# EE209_Schematic.net
KiCad netlist of a schematic drawn in Altium Designer
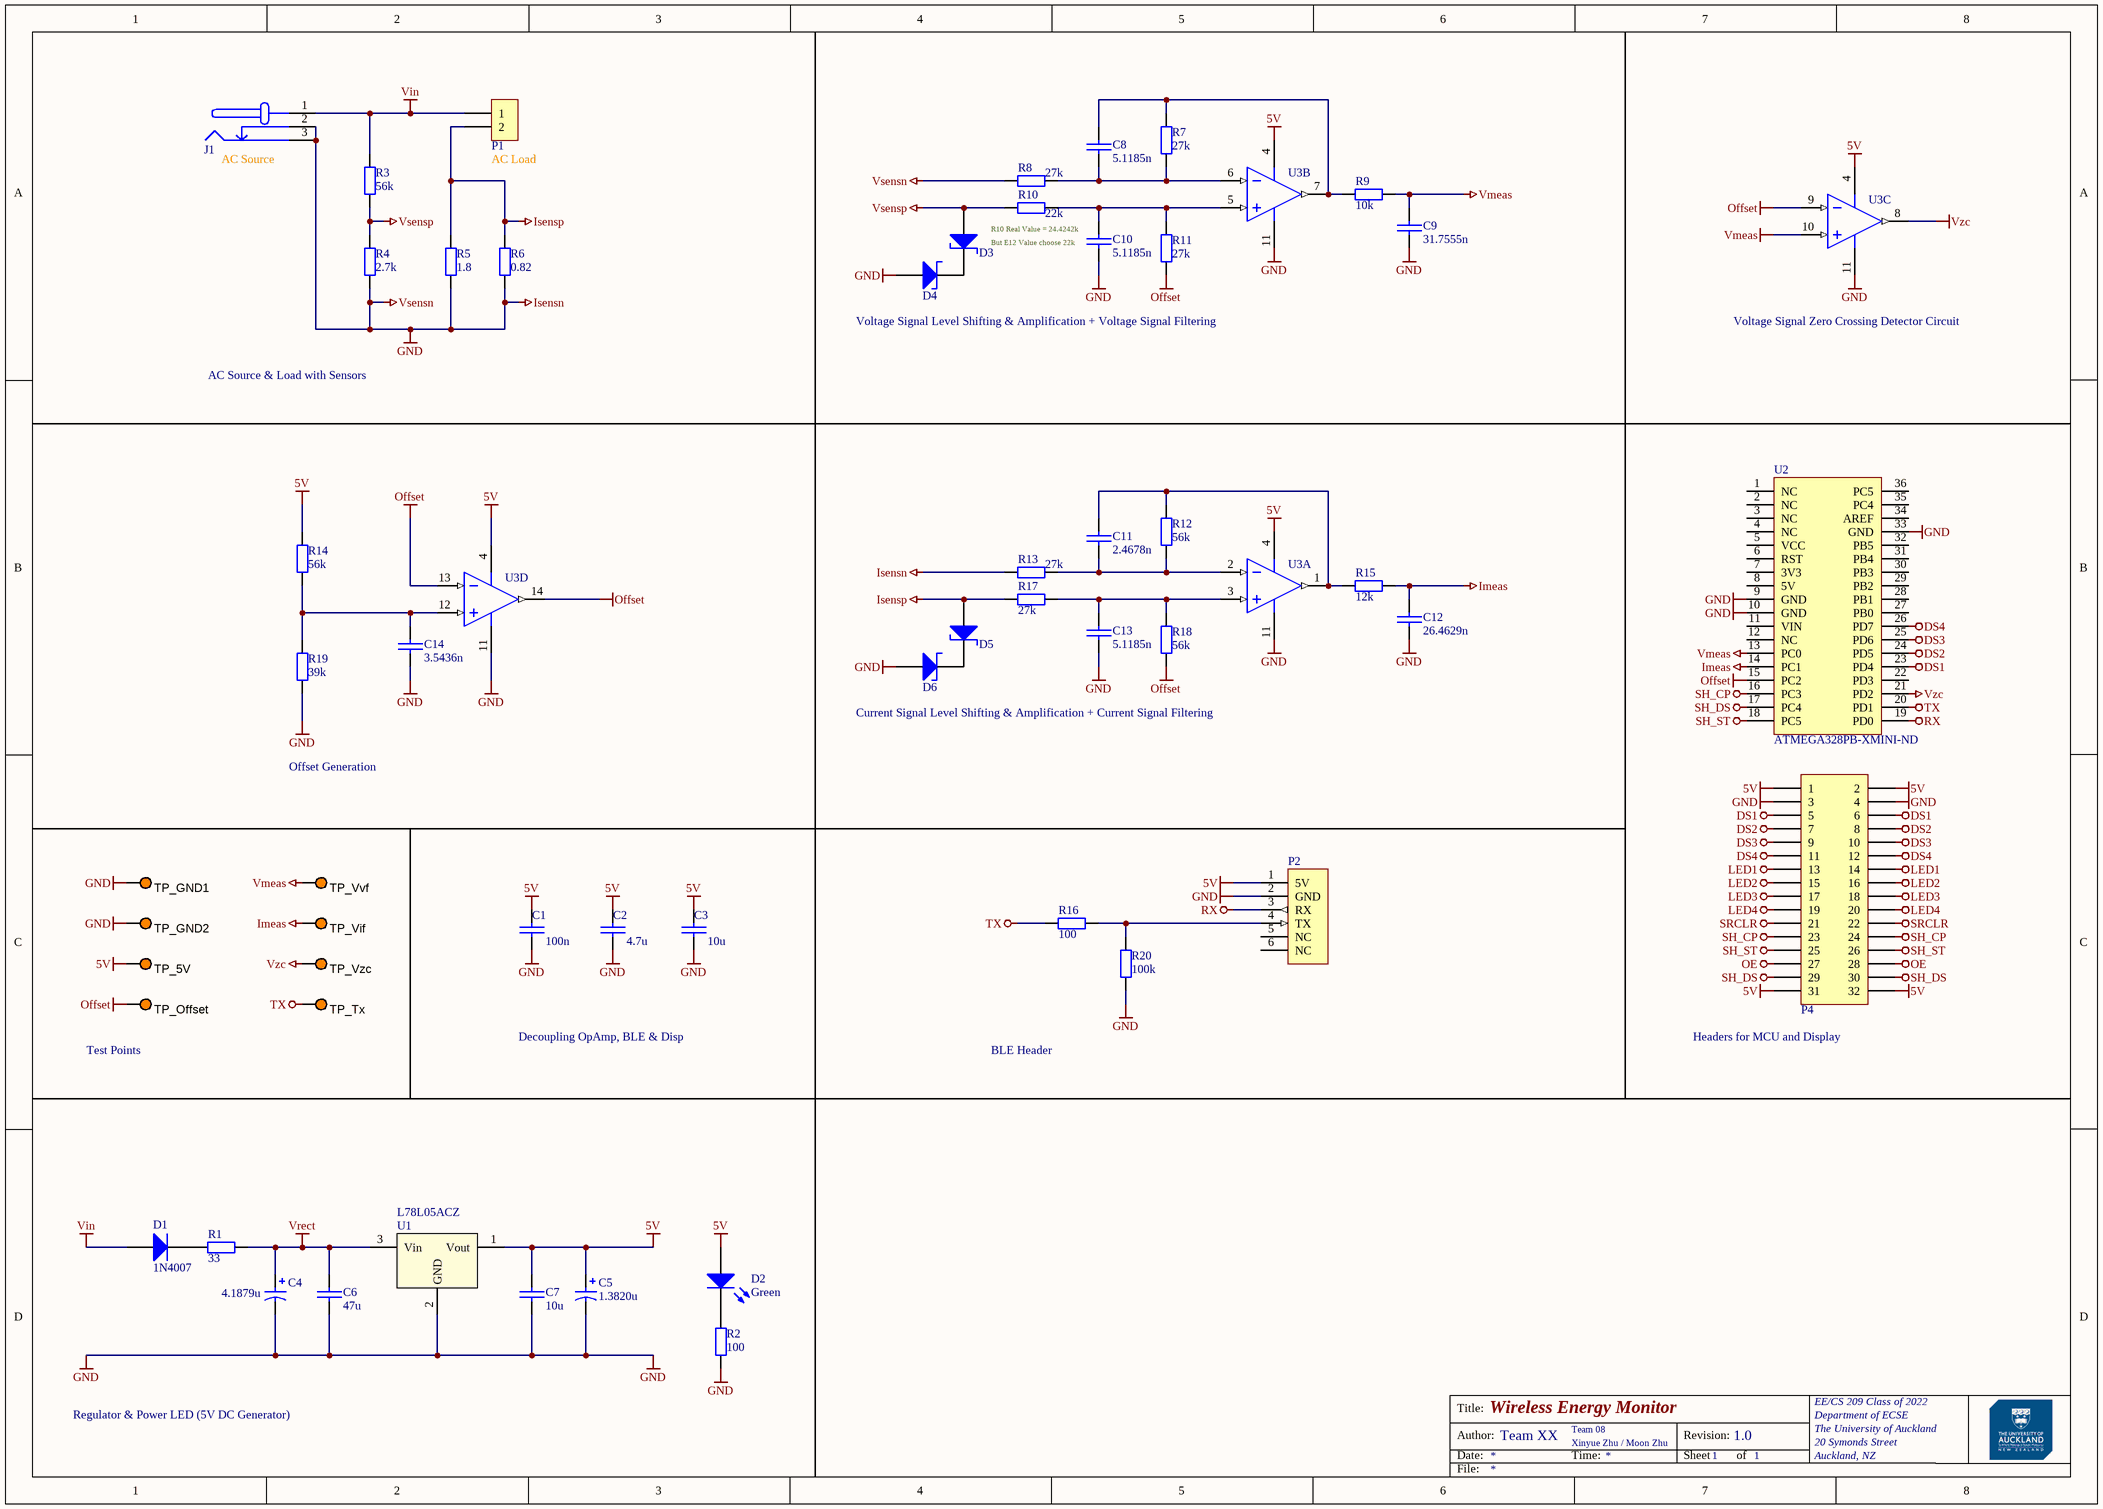
[diagram p0: EE209_Schematic.SchDoc]

(export (version "E")
  (design (tool "Eeschema 10.0.6"))
  (components
    (comp (ref "C1")
      (value "100n")
      (footprint "CCAP-5P0")
      (description "TH ceramic capacitor with 5mm pitch")
      (libsource (lib "EE209_Library") (part "CerCap_TH_5P0"))
    )
    (comp (ref "C2")
      (value "4.7u")
      (footprint "CCAP-5P0")
      (description "TH ceramic capacitor with 5mm pitch")
      (libsource (lib "EE209_Library") (part "CerCap_TH_5P0"))
    )
    (comp (ref "C3")
      (value "10u")
      (footprint "CCAP-5P0")
      (description "TH ceramic capacitor with 5mm pitch")
      (libsource (lib "EE209_Library") (part "CerCap_TH_5P0"))
    )
    (comp (ref "C4")
      (value "4.1879u")
      (footprint "CAP-RAD-2.5mm Pitch")
      (description "Electrolytic capacitor with radial package, 2mm pitch and 5.2mm diameter")
      (fields (field (name "PUBLISHER") "Altium Limited"))
      (libsource (lib "EE209_Library") (part "ElecCap_TH_2P0"))
    )
    (comp (ref "C5")
      (value "1.3820u")
      (footprint "CAP-RAD-2.5mm Pitch")
      (description "Electrolytic capacitor with radial package, 2mm pitch and 5.2mm diameter")
      (fields (field (name "PUBLISHER") "Altium Limited"))
      (libsource (lib "EE209_Library") (part "ElecCap_TH_2P0"))
    )
    (comp (ref "C6")
      (value "47u")
      (footprint "CCAP-5P0")
      (description "TH ceramic capacitor with 5mm pitch")
      (libsource (lib "EE209_Library") (part "CerCap_TH_5P0"))
    )
    (comp (ref "C7")
      (value "10u")
      (footprint "CCAP-5P0")
      (description "TH ceramic capacitor with 5mm pitch")
      (libsource (lib "EE209_Library") (part "CerCap_TH_5P0"))
    )
    (comp (ref "C8")
      (value "5.1185n")
      (footprint "CCAP-5P0")
      (description "TH ceramic capacitor with 5mm pitch")
      (libsource (lib "EE209_Library") (part "CerCap_TH_5P0"))
    )
    (comp (ref "C9")
      (value "31.7555n")
      (footprint "CCAP-5P0")
      (description "TH ceramic capacitor with 5mm pitch")
      (libsource (lib "EE209_Library") (part "CerCap_TH_5P0"))
    )
    (comp (ref "C10")
      (value "5.1185n")
      (footprint "CCAP-5P0")
      (description "TH ceramic capacitor with 5mm pitch")
      (libsource (lib "EE209_Library") (part "CerCap_TH_5P0"))
    )
    (comp (ref "C11")
      (value "2.4678n")
      (footprint "CCAP-5P0")
      (description "TH ceramic capacitor with 5mm pitch")
      (libsource (lib "EE209_Library") (part "CerCap_TH_5P0"))
    )
    (comp (ref "C12")
      (value "26.4629n")
      (footprint "CCAP-5P0")
      (description "TH ceramic capacitor with 5mm pitch")
      (libsource (lib "EE209_Library") (part "CerCap_TH_5P0"))
    )
    (comp (ref "C13")
      (value "5.1185n")
      (footprint "CCAP-5P0")
      (description "TH ceramic capacitor with 5mm pitch")
      (libsource (lib "EE209_Library") (part "CerCap_TH_5P0"))
    )
    (comp (ref "C14")
      (value "3.5436n")
      (footprint "CCAP-5P0")
      (description "TH ceramic capacitor with 5mm pitch")
      (libsource (lib "EE209_Library") (part "CerCap_TH_5P0"))
    )
    (comp (ref "D1")
      (value "1N4007")
      (footprint "1N4007-MFG")
      (description "1N4007 1000V standard axial diode")
      (libsource (lib "EE209_Library") (part "1N4007_TH_4AX0"))
    )
    (comp (ref "D2")
      (value "Green")
      (footprint "LED")
      (description "Typical throughole GaAs LED with 2.54mm pitch")
      (fields (field (name "MANUFACTURER") "Generic Components") (field (name "PUBLISHER") "Altium Limited"))
      (libsource (lib "EE209_Library") (part "LED_TH_2P54"))
    )
    (comp (ref "D3")
      (value "BZX79-CXVX")
      (footprint "AXIAL-Zener-0.4")
      (description "Axial zener diode BZX79 series")
      (fields
        (field (name "MANUFACTURER") "Nexperia USA Inc.")
        (field (name "MANUFACTURER PART NUMBER") "BZX79-C4V7,143")
      )
      (libsource (lib "EE209_Library") (part "Zener_TH_4AX0"))
    )
    (comp (ref "D4")
      (value "BZX79-CXVX")
      (footprint "AXIAL-Zener-0.4")
      (description "Axial zener diode BZX79 series")
      (fields
        (field (name "MANUFACTURER") "Nexperia USA Inc.")
        (field (name "MANUFACTURER PART NUMBER") "BZX79-C4V7,143")
      )
      (libsource (lib "EE209_Library") (part "Zener_TH_4AX0"))
    )
    (comp (ref "D5")
      (value "BZX79-CXVX")
      (footprint "AXIAL-Zener-0.4")
      (description "Axial zener diode BZX79 series")
      (fields
        (field (name "MANUFACTURER") "Nexperia USA Inc.")
        (field (name "MANUFACTURER PART NUMBER") "BZX79-C4V7,143")
      )
      (libsource (lib "EE209_Library") (part "Zener_TH_4AX0"))
    )
    (comp (ref "D6")
      (value "BZX79-CXVX")
      (footprint "AXIAL-Zener-0.4")
      (description "Axial zener diode BZX79 series")
      (fields
        (field (name "MANUFACTURER") "Nexperia USA Inc.")
        (field (name "MANUFACTURER PART NUMBER") "BZX79-C4V7,143")
      )
      (libsource (lib "EE209_Library") (part "Zener_TH_4AX0"))
    )
    (comp (ref "J1")
      (value "DC barrel jack")
      (footprint "AC-Socket")
      (description "DC barrel jack connection to AC source")
      (libsource (lib "EE209_Library") (part "AC_Input"))
    )
    (comp (ref "P1")
      (value "Dual Banana Plugs")
      (footprint "Dual Banana Plug")
      (description "Dual banana plugs connection to the AC load")
      (fields (field (name "PUBLISHER") "Altium Limited"))
      (libsource (lib "EE209_Library") (part "AC_Output"))
    )
    (comp (ref "P2")
      (value "BLE Module Header")
      (footprint "HM10_HDR1X6")
      (description "2.54mm pitch 6-pin header for BLE module")
      (fields (field (name "PUBLISHER") "Altium Limited"))
      (libsource (lib "EE209_Library") (part "BLEModule_TH"))
    )
    (comp (ref "P4")
      (value "Display")
      (footprint "Display")
      (description "16-Pin Header Connecting Display")
      (libsource (lib "EE209_Library") (part "Display"))
    )
    (comp (ref "R1")
      (value "33")
      (footprint "AXIAL-0.4")
      (description "Through hole resistor")
      (fields (field (name "PUBLISHER") "Altium Limited"))
      (libsource (lib "") (part "Res_TH_0AX4_3"))
    )
    (comp (ref "R2")
      (value "100")
      (footprint "AXIAL-0.4")
      (description "Through hole resistor")
      (fields (field (name "PUBLISHER") "Altium Limited"))
      (libsource (lib "") (part "Res_TH_0AX4_1"))
    )
    (comp (ref "R3")
      (value "56k")
      (footprint "AXIAL-0.4")
      (description "Through hole resistor")
      (fields (field (name "PUBLISHER") "Altium Limited"))
      (libsource (lib "") (part "Res_TH_0AX4_1"))
    )
    (comp (ref "R4")
      (value "2.7k")
      (footprint "AXIAL-0.4")
      (description "Through hole resistor")
      (fields (field (name "PUBLISHER") "Altium Limited"))
      (libsource (lib "") (part "Res_TH_0AX4_1"))
    )
    (comp (ref "R5")
      (value "1.8")
      (footprint "AXIAL-0.4")
      (description "Through hole resistor")
      (fields (field (name "PUBLISHER") "Altium Limited"))
      (libsource (lib "") (part "Res_TH_0AX4_1"))
    )
    (comp (ref "R6")
      (value "0.82")
      (footprint "AXIAL-0.4")
      (description "Through hole resistor")
      (fields (field (name "PUBLISHER") "Altium Limited"))
      (libsource (lib "") (part "Res_TH_0AX4_1"))
    )
    (comp (ref "R7")
      (value "27k")
      (footprint "AXIAL-0.4")
      (description "Through hole resistor")
      (fields (field (name "PUBLISHER") "Altium Limited"))
      (libsource (lib "") (part "Res_TH_0AX4_1"))
    )
    (comp (ref "R8")
      (value "27k")
      (footprint "AXIAL-0.4")
      (description "Through hole resistor")
      (fields (field (name "PUBLISHER") "Altium Limited"))
      (libsource (lib "") (part "Res_TH_0AX4_2"))
    )
    (comp (ref "R9")
      (value "10k")
      (footprint "AXIAL-0.4")
      (description "Through hole resistor")
      (fields (field (name "PUBLISHER") "Altium Limited"))
      (libsource (lib "") (part "Res_TH_0AX4_2"))
    )
    (comp (ref "R10")
      (value "22k")
      (footprint "AXIAL-0.4")
      (description "Through hole resistor")
      (fields (field (name "PUBLISHER") "Altium Limited"))
      (libsource (lib "") (part "Res_TH_0AX4_2"))
    )
    (comp (ref "R11")
      (value "27k")
      (footprint "AXIAL-0.4")
      (description "Through hole resistor")
      (fields (field (name "PUBLISHER") "Altium Limited"))
      (libsource (lib "") (part "Res_TH_0AX4_1"))
    )
    (comp (ref "R12")
      (value "56k")
      (footprint "AXIAL-0.4")
      (description "Through hole resistor")
      (fields (field (name "PUBLISHER") "Altium Limited"))
      (libsource (lib "") (part "Res_TH_0AX4_1"))
    )
    (comp (ref "R13")
      (value "27k")
      (footprint "AXIAL-0.4")
      (description "Through hole resistor")
      (fields (field (name "PUBLISHER") "Altium Limited"))
      (libsource (lib "") (part "Res_TH_0AX4_2"))
    )
    (comp (ref "R14")
      (value "56k")
      (footprint "AXIAL-0.4")
      (description "Through hole resistor")
      (fields (field (name "PUBLISHER") "Altium Limited"))
      (libsource (lib "EE209_Library") (part "Res_TH_0AX4"))
    )
    (comp (ref "R15")
      (value "12k")
      (footprint "AXIAL-0.4")
      (description "Through hole resistor")
      (fields (field (name "PUBLISHER") "Altium Limited"))
      (libsource (lib "") (part "Res_TH_0AX4_2"))
    )
    (comp (ref "R16")
      (value "100")
      (footprint "AXIAL-0.4")
      (description "Through hole resistor")
      (fields (field (name "PUBLISHER") "Altium Limited"))
      (libsource (lib "") (part "Res_TH_0AX4_3"))
    )
    (comp (ref "R17")
      (value "27k")
      (footprint "AXIAL-0.4")
      (description "Through hole resistor")
      (fields (field (name "PUBLISHER") "Altium Limited"))
      (libsource (lib "") (part "Res_TH_0AX4_2"))
    )
    (comp (ref "R18")
      (value "56k")
      (footprint "AXIAL-0.4")
      (description "Through hole resistor")
      (fields (field (name "PUBLISHER") "Altium Limited"))
      (libsource (lib "") (part "Res_TH_0AX4_1"))
    )
    (comp (ref "R19")
      (value "39k")
      (footprint "AXIAL-0.4")
      (description "Through hole resistor")
      (fields (field (name "PUBLISHER") "Altium Limited"))
      (libsource (lib "") (part "Res_TH_0AX4_1"))
    )
    (comp (ref "R20")
      (value "100k")
      (footprint "AXIAL-0.4")
      (description "Through hole resistor")
      (fields (field (name "PUBLISHER") "Altium Limited"))
      (libsource (lib "") (part "Res_TH_0AX4_1"))
    )
    (comp (ref "TP_5V")
      (value "5003")
      (footprint "TP_TH")
      (description "Test Point, Orange, 1-Pin THD, RoHS")
      (libsource (lib "EE209_Library") (part "TestPoint"))
    )
    (comp (ref "TP_GND1")
      (value "5003")
      (footprint "TP_TH")
      (description "Test Point, Orange, 1-Pin THD, RoHS")
      (libsource (lib "EE209_Library") (part "TestPoint"))
    )
    (comp (ref "TP_GND2")
      (value "5003")
      (footprint "TP_TH")
      (description "Test Point, Orange, 1-Pin THD, RoHS")
      (libsource (lib "EE209_Library") (part "TestPoint"))
    )
    (comp (ref "TP_Offset")
      (value "5003")
      (footprint "TP_TH")
      (description "Test Point, Orange, 1-Pin THD, RoHS")
      (libsource (lib "EE209_Library") (part "TestPoint"))
    )
    (comp (ref "TP_Tx")
      (value "5003")
      (footprint "TP_TH")
      (description "Test Point, Orange, 1-Pin THD, RoHS")
      (libsource (lib "EE209_Library") (part "TestPoint"))
    )
    (comp (ref "TP_Vif")
      (value "5003")
      (footprint "TP_TH")
      (description "Test Point, Orange, 1-Pin THD, RoHS")
      (libsource (lib "EE209_Library") (part "TestPoint"))
    )
    (comp (ref "TP_Vvf")
      (value "5003")
      (footprint "TP_TH")
      (description "Test Point, Orange, 1-Pin THD, RoHS")
      (libsource (lib "EE209_Library") (part "TestPoint"))
    )
    (comp (ref "TP_Vzc")
      (value "5003")
      (footprint "TP_TH")
      (description "Test Point, Orange, 1-Pin THD, RoHS")
      (libsource (lib "EE209_Library") (part "TestPoint"))
    )
    (comp (ref "U1")
      (value "L78L05ACZ")
      (footprint "TO-92")
      (description "Voltage Regulator 5V")
      (fields
        (field (name "MANUFACTURER") "ON Semiconductor")
        (field (name "MANUFACTURER PART NUMBER") "LM78L05ACZX")
      )
      (libsource (lib "EE209_Library") (part "L78L05_TH_TO92"))
    )
    (comp (ref "U2")
      (value "ATmega328PB Xplained Mini Header")
      (footprint "ATmeg328P Xplained")
      (description "Dual 18-pin headers connecting to ATmega328PB Xplained Mini")
      (fields
        (field (name "MANUFACTURER") "Microchip Technology")
        (field (name "MANUFACTURER PART NUMBER") "ATMEGA328PB-XMINI")
        (field (name "SUPPLIER PART NUMBER 1") "ATMEGA328PB-XMINI-ND")
      )
      (libsource (lib "EE209_Library") (part "ATmega328PBXplained_TH"))
    )
    (comp (ref "U3")
      (value "LM324")
      (footprint "DIP-14")
      (description "IC OPAMP GP 14DIP")
      (fields
        (field (name "MANUFACTURER") "ON Semiconductor")
        (field (name "MANUFACTURER PART NUMBER") "LM324N")
      )
      (libsource (lib "EE209_Library") (part "LM324N_TH_DIP16"))
    )
  )
  (nets
    (net (code "1") (name "5V") (class "Default")
      (node (ref "C1") (pin "1") (pinfunction "1_1") (pintype "passive"))
      (node (ref "C2") (pin "1") (pinfunction "1_1") (pintype "passive"))
      (node (ref "C3") (pin "1") (pinfunction "1_1") (pintype "passive"))
      (node (ref "C5") (pin "1") (pinfunction "1_1") (pintype "passive"))
      (node (ref "C7") (pin "1") (pinfunction "1_1") (pintype "passive"))
      (node (ref "D2") (pin "1") (pinfunction "A_1") (pintype "passive"))
      (node (ref "P2") (pin "1") (pinfunction "5V_1") (pintype "passive"))
      (node (ref "P4") (pin "1") (pinfunction "1_1") (pintype "passive"))
      (node (ref "P4") (pin "2") (pinfunction "2_2") (pintype "passive"))
      (node (ref "P4") (pin "31") (pinfunction "31_31") (pintype "passive"))
      (node (ref "P4") (pin "32") (pinfunction "32_32") (pintype "passive"))
      (node (ref "R14") (pin "1") (pinfunction "1_1") (pintype "passive"))
      (node (ref "TP_5V") (pin "1") (pinfunction "1_1") (pintype "passive"))
      (node (ref "U1") (pin "1") (pinfunction "Vout_1") (pintype "passive"))
      (node (ref "U3") (pin "4") (pinfunction "VDD_4") (pintype "power_in"))
    )
    (net (code "2") (name "DS1") (class "Default")
      (node (ref "P4") (pin "5") (pinfunction "5_5") (pintype "passive"))
      (node (ref "P4") (pin "6") (pinfunction "6_6") (pintype "passive"))
      (node (ref "U2") (pin "23") (pinfunction "PD4_23") (pintype "passive"))
    )
    (net (code "3") (name "DS2") (class "Default")
      (node (ref "P4") (pin "7") (pinfunction "7_7") (pintype "passive"))
      (node (ref "P4") (pin "8") (pinfunction "8_8") (pintype "passive"))
      (node (ref "U2") (pin "24") (pinfunction "PD5_24") (pintype "passive"))
    )
    (net (code "4") (name "DS3") (class "Default")
      (node (ref "P4") (pin "10") (pinfunction "10_10") (pintype "passive"))
      (node (ref "P4") (pin "9") (pinfunction "9_9") (pintype "passive"))
      (node (ref "U2") (pin "25") (pinfunction "PD6_25") (pintype "passive"))
    )
    (net (code "5") (name "DS4") (class "Default")
      (node (ref "P4") (pin "11") (pinfunction "11_11") (pintype "passive"))
      (node (ref "P4") (pin "12") (pinfunction "12_12") (pintype "passive"))
      (node (ref "U2") (pin "26") (pinfunction "PD7_26") (pintype "passive"))
    )
    (net (code "6") (name "GND") (class "Default")
      (node (ref "C1") (pin "2") (pinfunction "2_2") (pintype "passive"))
      (node (ref "C10") (pin "2") (pinfunction "2_2") (pintype "passive"))
      (node (ref "C12") (pin "2") (pinfunction "2_2") (pintype "passive"))
      (node (ref "C13") (pin "2") (pinfunction "2_2") (pintype "passive"))
      (node (ref "C14") (pin "2") (pinfunction "2_2") (pintype "passive"))
      (node (ref "C2") (pin "2") (pinfunction "2_2") (pintype "passive"))
      (node (ref "C3") (pin "2") (pinfunction "2_2") (pintype "passive"))
      (node (ref "C4") (pin "2") (pinfunction "2_2") (pintype "passive"))
      (node (ref "C5") (pin "2") (pinfunction "2_2") (pintype "passive"))
      (node (ref "C6") (pin "2") (pinfunction "2_2") (pintype "passive"))
      (node (ref "C7") (pin "2") (pinfunction "2_2") (pintype "passive"))
      (node (ref "C9") (pin "2") (pinfunction "2_2") (pintype "passive"))
      (node (ref "D4") (pin "1") (pinfunction "A_1") (pintype "passive"))
      (node (ref "D6") (pin "1") (pinfunction "A_1") (pintype "passive"))
      (node (ref "J1") (pin "2") (pinfunction "GND_ALT_2") (pintype "power_in"))
      (node (ref "J1") (pin "3") (pinfunction "GND_3") (pintype "power_in"))
      (node (ref "P2") (pin "2") (pinfunction "GND_2") (pintype "passive"))
      (node (ref "P4") (pin "3") (pinfunction "3_3") (pintype "passive"))
      (node (ref "P4") (pin "4") (pinfunction "4_4") (pintype "passive"))
      (node (ref "R13") (pin "2") (pinfunction "2_2") (pintype "passive"))
      (node (ref "R19") (pin "1") (pinfunction "1_1") (pintype "passive"))
      (node (ref "R2") (pin "1") (pinfunction "1_1") (pintype "passive"))
      (node (ref "R20") (pin "1") (pinfunction "1_1") (pintype "passive"))
      (node (ref "R4") (pin "1") (pinfunction "1_1") (pintype "passive"))
      (node (ref "R5") (pin "1") (pinfunction "1_1") (pintype "passive"))
      (node (ref "R6") (pin "1") (pinfunction "1_1") (pintype "passive"))
      (node (ref "R8") (pin "2") (pinfunction "2_2") (pintype "passive"))
      (node (ref "TP_GND1") (pin "1") (pinfunction "1_1") (pintype "passive"))
      (node (ref "TP_GND2") (pin "1") (pinfunction "1_1") (pintype "passive"))
      (node (ref "U1") (pin "2") (pinfunction "GND_2") (pintype "passive"))
      (node (ref "U2") (pin "10") (pinfunction "GND_10") (pintype "power_in"))
      (node (ref "U2") (pin "33") (pinfunction "GND_33") (pintype "passive"))
      (node (ref "U2") (pin "9") (pinfunction "GND_9") (pintype "power_in"))
      (node (ref "U3") (pin "11") (pinfunction "VSS_11") (pintype "power_in"))
    )
    (net (code "7") (name "Imeas") (class "Default")
      (node (ref "C12") (pin "1") (pinfunction "1_1") (pintype "passive"))
      (node (ref "R15") (pin "1") (pinfunction "1_1") (pintype "passive"))
      (node (ref "TP_Vif") (pin "1") (pinfunction "1_1") (pintype "passive"))
      (node (ref "U2") (pin "14") (pinfunction "PC1_14") (pintype "passive"))
    )
    (net (code "8") (name "Isensp") (class "Default")
      (node (ref "D5") (pin "1") (pinfunction "A_1") (pintype "passive"))
      (node (ref "P1") (pin "2") (pinfunction "2_2") (pintype "passive"))
      (node (ref "R17") (pin "2") (pinfunction "2_2") (pintype "passive"))
      (node (ref "R5") (pin "2") (pinfunction "2_2") (pintype "passive"))
      (node (ref "R6") (pin "2") (pinfunction "2_2") (pintype "passive"))
    )
    (net (code "9") (name "LED1") (class "Default")
      (node (ref "P4") (pin "13") (pinfunction "13_13") (pintype "passive"))
      (node (ref "P4") (pin "14") (pinfunction "14_14") (pintype "passive"))
    )
    (net (code "10") (name "LED2") (class "Default")
      (node (ref "P4") (pin "15") (pinfunction "15_15") (pintype "passive"))
      (node (ref "P4") (pin "16") (pinfunction "16_16") (pintype "passive"))
    )
    (net (code "11") (name "LED3") (class "Default")
      (node (ref "P4") (pin "17") (pinfunction "17_17") (pintype "passive"))
      (node (ref "P4") (pin "18") (pinfunction "18_18") (pintype "passive"))
    )
    (net (code "12") (name "LED4") (class "Default")
      (node (ref "P4") (pin "19") (pinfunction "19_19") (pintype "passive"))
      (node (ref "P4") (pin "20") (pinfunction "20_20") (pintype "passive"))
    )
    (net (code "13") (name "Net-(D1-K)") (class "Default")
      (node (ref "D1") (pin "2") (pinfunction "K_2") (pintype "passive"))
      (node (ref "R1") (pin "1") (pinfunction "1_1") (pintype "passive"))
    )
    (net (code "14") (name "Net-(D2-K)") (class "Default")
      (node (ref "D2") (pin "2") (pinfunction "K_2") (pintype "passive"))
      (node (ref "R2") (pin "2") (pinfunction "2_2") (pintype "passive"))
    )
    (net (code "15") (name "Net-(D3-K)") (class "Default")
      (node (ref "D3") (pin "2") (pinfunction "K_2") (pintype "passive"))
      (node (ref "D4") (pin "2") (pinfunction "K_2") (pintype "passive"))
    )
    (net (code "16") (name "Net-(D5-K)") (class "Default")
      (node (ref "D5") (pin "2") (pinfunction "K_2") (pintype "passive"))
      (node (ref "D6") (pin "2") (pinfunction "K_2") (pintype "passive"))
    )
    (net (code "17") (name "Net-(P2-TX)") (class "Default")
      (node (ref "P2") (pin "4") (pinfunction "TX_4") (pintype "input"))
      (node (ref "R16") (pin "2") (pinfunction "2_2") (pintype "passive"))
      (node (ref "R20") (pin "2") (pinfunction "2_2") (pintype "passive"))
    )
    (net (code "18") (name "Net-(U3A-VINA+)") (class "Default")
      (node (ref "C13") (pin "1") (pinfunction "1_1") (pintype "passive"))
      (node (ref "R17") (pin "1") (pinfunction "1_1") (pintype "passive"))
      (node (ref "R18") (pin "2") (pinfunction "2_2") (pintype "passive"))
      (node (ref "U3") (pin "3") (pinfunction "VINA+_3") (pintype "input"))
    )
    (net (code "19") (name "Net-(U3A-VINA-)") (class "Default")
      (node (ref "C11") (pin "2") (pinfunction "2_2") (pintype "passive"))
      (node (ref "R12") (pin "1") (pinfunction "1_1") (pintype "passive"))
      (node (ref "R13") (pin "1") (pinfunction "1_1") (pintype "passive"))
      (node (ref "U3") (pin "2") (pinfunction "VINA-_2") (pintype "input"))
    )
    (net (code "20") (name "Net-(U3A-VOUTA)") (class "Default")
      (node (ref "C11") (pin "1") (pinfunction "1_1") (pintype "passive"))
      (node (ref "R12") (pin "2") (pinfunction "2_2") (pintype "passive"))
      (node (ref "R15") (pin "2") (pinfunction "2_2") (pintype "passive"))
      (node (ref "U3") (pin "1") (pinfunction "VOUTA_1") (pintype "output"))
    )
    (net (code "21") (name "Net-(U3B-VINB+)") (class "Default")
      (node (ref "C10") (pin "1") (pinfunction "1_1") (pintype "passive"))
      (node (ref "R10") (pin "1") (pinfunction "1_1") (pintype "passive"))
      (node (ref "R11") (pin "2") (pinfunction "2_2") (pintype "passive"))
      (node (ref "U3") (pin "5") (pinfunction "VINB+_5") (pintype "input"))
    )
    (net (code "22") (name "Net-(U3B-VINB-)") (class "Default")
      (node (ref "C8") (pin "2") (pinfunction "2_2") (pintype "passive"))
      (node (ref "R7") (pin "1") (pinfunction "1_1") (pintype "passive"))
      (node (ref "R8") (pin "1") (pinfunction "1_1") (pintype "passive"))
      (node (ref "U3") (pin "6") (pinfunction "VINB-_6") (pintype "input"))
    )
    (net (code "23") (name "Net-(U3B-VOUTB)") (class "Default")
      (node (ref "C8") (pin "1") (pinfunction "1_1") (pintype "passive"))
      (node (ref "R7") (pin "2") (pinfunction "2_2") (pintype "passive"))
      (node (ref "R9") (pin "2") (pinfunction "2_2") (pintype "passive"))
      (node (ref "U3") (pin "7") (pinfunction "VOUTB_7") (pintype "output"))
    )
    (net (code "24") (name "Net-(U3D-VIND+)") (class "Default")
      (node (ref "C14") (pin "1") (pinfunction "1_1") (pintype "passive"))
      (node (ref "R14") (pin "2") (pinfunction "2_2") (pintype "passive"))
      (node (ref "R19") (pin "2") (pinfunction "2_2") (pintype "passive"))
      (node (ref "U3") (pin "12") (pinfunction "VIND+_12") (pintype "input"))
    )
    (net (code "25") (name "OE") (class "Default")
      (node (ref "P4") (pin "27") (pinfunction "27_27") (pintype "passive"))
      (node (ref "P4") (pin "28") (pinfunction "28_28") (pintype "passive"))
    )
    (net (code "26") (name "Offset") (class "Default")
      (node (ref "R11") (pin "1") (pinfunction "1_1") (pintype "passive"))
      (node (ref "R18") (pin "1") (pinfunction "1_1") (pintype "passive"))
      (node (ref "TP_Offset") (pin "1") (pinfunction "1_1") (pintype "passive"))
      (node (ref "U2") (pin "15") (pinfunction "PC2_15") (pintype "passive"))
      (node (ref "U3") (pin "13") (pinfunction "VIND-_13") (pintype "input"))
      (node (ref "U3") (pin "14") (pinfunction "VOUTD_14") (pintype "output"))
      (node (ref "U3") (pin "9") (pinfunction "VINC-_9") (pintype "input"))
    )
    (net (code "27") (name "RX") (class "Default")
      (node (ref "P2") (pin "3") (pinfunction "RX_3") (pintype "output"))
      (node (ref "U2") (pin "19") (pinfunction "PD0_19") (pintype "passive"))
    )
    (net (code "28") (name "SH_CP") (class "Default")
      (node (ref "P4") (pin "23") (pinfunction "23_23") (pintype "passive"))
      (node (ref "P4") (pin "24") (pinfunction "24_24") (pintype "passive"))
      (node (ref "U2") (pin "16") (pinfunction "PC3_16") (pintype "passive"))
    )
    (net (code "29") (name "SH_DS") (class "Default")
      (node (ref "P4") (pin "29") (pinfunction "29_29") (pintype "passive"))
      (node (ref "P4") (pin "30") (pinfunction "30_30") (pintype "passive"))
      (node (ref "U2") (pin "17") (pinfunction "PC4_17") (pintype "passive"))
    )
    (net (code "30") (name "SH_ST") (class "Default")
      (node (ref "P4") (pin "25") (pinfunction "25_25") (pintype "passive"))
      (node (ref "P4") (pin "26") (pinfunction "26_26") (pintype "passive"))
      (node (ref "U2") (pin "18") (pinfunction "PC5_18") (pintype "passive"))
    )
    (net (code "31") (name "SRCLR") (class "Default")
      (node (ref "P4") (pin "21") (pinfunction "21_21") (pintype "passive"))
      (node (ref "P4") (pin "22") (pinfunction "22_22") (pintype "passive"))
    )
    (net (code "32") (name "TX") (class "Default")
      (node (ref "R16") (pin "1") (pinfunction "1_1") (pintype "passive"))
      (node (ref "TP_Tx") (pin "1") (pinfunction "1_1") (pintype "passive"))
      (node (ref "U2") (pin "20") (pinfunction "PD1_20") (pintype "passive"))
    )
    (net (code "33") (name "Vin") (class "Default")
      (node (ref "D1") (pin "1") (pinfunction "A_1") (pintype "passive"))
      (node (ref "J1") (pin "1") (pinfunction "VCC_1") (pintype "power_in"))
      (node (ref "P1") (pin "1") (pinfunction "1_1") (pintype "passive"))
      (node (ref "R3") (pin "2") (pinfunction "2_2") (pintype "passive"))
    )
    (net (code "34") (name "Vmeas") (class "Default")
      (node (ref "C9") (pin "1") (pinfunction "1_1") (pintype "passive"))
      (node (ref "R9") (pin "1") (pinfunction "1_1") (pintype "passive"))
      (node (ref "TP_Vvf") (pin "1") (pinfunction "1_1") (pintype "passive"))
      (node (ref "U2") (pin "13") (pinfunction "PC0_13") (pintype "passive"))
      (node (ref "U3") (pin "10") (pinfunction "VINC+_10") (pintype "input"))
    )
    (net (code "35") (name "Vrect") (class "Default")
      (node (ref "C4") (pin "1") (pinfunction "1_1") (pintype "passive"))
      (node (ref "C6") (pin "1") (pinfunction "1_1") (pintype "passive"))
      (node (ref "R1") (pin "2") (pinfunction "2_2") (pintype "passive"))
      (node (ref "U1") (pin "3") (pinfunction "Vin_3") (pintype "passive"))
    )
    (net (code "36") (name "Vsensp") (class "Default")
      (node (ref "D3") (pin "1") (pinfunction "A_1") (pintype "passive"))
      (node (ref "R10") (pin "2") (pinfunction "2_2") (pintype "passive"))
      (node (ref "R3") (pin "1") (pinfunction "1_1") (pintype "passive"))
      (node (ref "R4") (pin "2") (pinfunction "2_2") (pintype "passive"))
    )
    (net (code "37") (name "Vzc") (class "Default")
      (node (ref "TP_Vzc") (pin "1") (pinfunction "1_1") (pintype "passive"))
      (node (ref "U2") (pin "21") (pinfunction "PD2_21") (pintype "passive"))
      (node (ref "U3") (pin "8") (pinfunction "VOUTC_8") (pintype "output"))
    )
    (net (code "38") (name "unconnected-(P2-NC-Pad5)") (class "Default")
      (node (ref "P2") (pin "5") (pinfunction "NC_5") (pintype "passive"))
    )
    (net (code "39") (name "unconnected-(P2-NC-Pad6)") (class "Default")
      (node (ref "P2") (pin "6") (pinfunction "NC_6") (pintype "passive"))
    )
    (net (code "40") (name "unconnected-(U2-3V3-Pad7)") (class "Default")
      (node (ref "U2") (pin "7") (pinfunction "3V3_7") (pintype "passive"))
    )
    (net (code "41") (name "unconnected-(U2-5V-Pad8)") (class "Default")
      (node (ref "U2") (pin "8") (pinfunction "5V_8") (pintype "power_in"))
    )
    (net (code "42") (name "unconnected-(U2-AREF-Pad34)") (class "Default")
      (node (ref "U2") (pin "34") (pinfunction "AREF_34") (pintype "passive"))
    )
    (net (code "43") (name "unconnected-(U2-NC-Pad1)") (class "Default")
      (node (ref "U2") (pin "1") (pinfunction "NC_1") (pintype "passive"))
    )
    (net (code "44") (name "unconnected-(U2-NC-Pad2)") (class "Default")
      (node (ref "U2") (pin "2") (pinfunction "NC_2") (pintype "passive"))
    )
    (net (code "45") (name "unconnected-(U2-NC-Pad3)") (class "Default")
      (node (ref "U2") (pin "3") (pinfunction "NC_3") (pintype "passive"))
    )
    (net (code "46") (name "unconnected-(U2-NC-Pad4)") (class "Default")
      (node (ref "U2") (pin "4") (pinfunction "NC_4") (pintype "passive"))
    )
    (net (code "47") (name "unconnected-(U2-NC-Pad12)") (class "Default")
      (node (ref "U2") (pin "12") (pinfunction "NC_12") (pintype "passive"))
    )
    (net (code "48") (name "unconnected-(U2-PB0-Pad27)") (class "Default")
      (node (ref "U2") (pin "27") (pinfunction "PB0_27") (pintype "passive"))
    )
    (net (code "49") (name "unconnected-(U2-PB1-Pad28)") (class "Default")
      (node (ref "U2") (pin "28") (pinfunction "PB1_28") (pintype "passive"))
    )
    (net (code "50") (name "unconnected-(U2-PB2-Pad29)") (class "Default")
      (node (ref "U2") (pin "29") (pinfunction "PB2_29") (pintype "passive"))
    )
    (net (code "51") (name "unconnected-(U2-PB3-Pad30)") (class "Default")
      (node (ref "U2") (pin "30") (pinfunction "PB3_30") (pintype "passive"))
    )
    (net (code "52") (name "unconnected-(U2-PB4-Pad31)") (class "Default")
      (node (ref "U2") (pin "31") (pinfunction "PB4_31") (pintype "passive"))
    )
    (net (code "53") (name "unconnected-(U2-PB5-Pad32)") (class "Default")
      (node (ref "U2") (pin "32") (pinfunction "PB5_32") (pintype "passive"))
    )
    (net (code "54") (name "unconnected-(U2-PC4-Pad35)") (class "Default")
      (node (ref "U2") (pin "35") (pinfunction "PC4_35") (pintype "passive"))
    )
    (net (code "55") (name "unconnected-(U2-PC5-Pad36)") (class "Default")
      (node (ref "U2") (pin "36") (pinfunction "PC5_36") (pintype "passive"))
    )
    (net (code "56") (name "unconnected-(U2-PD3-Pad22)") (class "Default")
      (node (ref "U2") (pin "22") (pinfunction "PD3_22") (pintype "passive"))
    )
    (net (code "57") (name "unconnected-(U2-RST-Pad6)") (class "Default")
      (node (ref "U2") (pin "6") (pinfunction "RST_6") (pintype "passive"))
    )
    (net (code "58") (name "unconnected-(U2-VCC-Pad5)") (class "Default")
      (node (ref "U2") (pin "5") (pinfunction "VCC_5") (pintype "power_in"))
    )
    (net (code "59") (name "unconnected-(U2-VIN-Pad11)") (class "Default")
      (node (ref "U2") (pin "11") (pinfunction "VIN_11") (pintype "power_in"))
    )
  )
)
